# Sheet1.net
KiCad netlist of a schematic drawn in Altium Designer
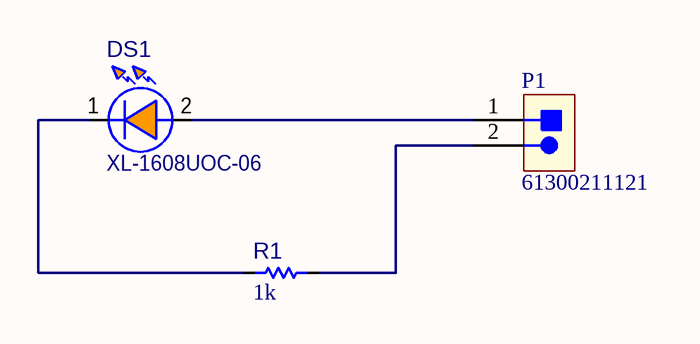
[diagram p0: Sheet1.SchDoc]

(export (version "E")
  (design (tool "Eeschema 10.0.6"))
  (components
    (comp (ref "DS1")
      (value "XL-1608UOC-06")
      (footprint "D_LED_0603")
      (description "LED Orange Clear")
      (libsource (lib "TEP_243-Altium_Library") (part "D_LED_ORANGE_0603"))
    )
    (comp (ref "P1")
      (value "61300211121")
      (footprint "CONN_HDR_2POS_100MILS_TH")
      (description "CONN HEADER 2POS 100MIL")
      (libsource (lib "TEP_243-AltiumLIB-Conn-TP-MH") (part "CONN-100MIL-HDR-01X02"))
    )
    (comp (ref "R1")
      (value "1k")
      (footprint "R_1608[0603]")
      (description "Resistor type 1")
      (fields (field (name "TOLERANCE") "1%") (field (name "Comment") "Res 1k 1% 0603"))
      (libsource (lib "TEP_243-Altium_DBLib") (part "resistor"))
    )
  )
  (nets
    (net (code "1") (name "Net-(DS1-A)") (class "Default")
      (node (ref "DS1") (pin "2") (pinfunction "A_2") (pintype "passive"))
      (node (ref "P1") (pin "1") (pinfunction "1_1") (pintype "passive"))
    )
    (net (code "2") (name "Net-(DS1-K)") (class "Default")
      (node (ref "DS1") (pin "1") (pinfunction "K_1") (pintype "passive"))
      (node (ref "R1") (pin "1") (pinfunction "1_1") (pintype "passive"))
    )
    (net (code "3") (name "Net-(P1-Pad2)") (class "Default")
      (node (ref "P1") (pin "2") (pinfunction "2_2") (pintype "passive"))
      (node (ref "R1") (pin "2") (pinfunction "2_2") (pintype "passive"))
    )
  )
)
